# LinReg5_3V3.net
KiCad netlist of a schematic drawn in Altium Designer
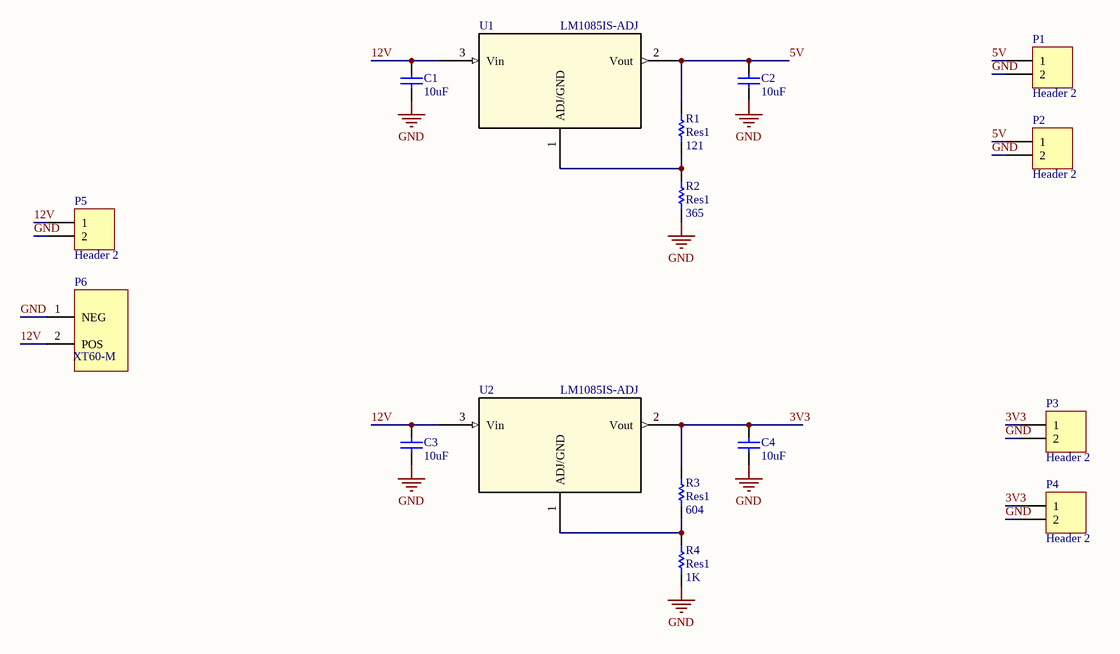
[diagram p0: LinReg5_3V3.SchDoc]

(export (version "E")
  (design (tool "Eeschema 10.0.6"))
  (components
    (comp (ref "C1")
      (value "10uF")
      (footprint "1206")
      (description "Capacitor")
      (fields (field (name "PUBLISHER") "Altium Limited"))
      (libsource (lib "Miscellaneous Devices") (part "Cap"))
    )
    (comp (ref "C2")
      (value "10uF")
      (footprint "1206")
      (description "Capacitor")
      (fields (field (name "PUBLISHER") "Altium Limited"))
      (libsource (lib "Miscellaneous Devices") (part "Cap"))
    )
    (comp (ref "C3")
      (value "10uF")
      (footprint "1206")
      (description "Capacitor")
      (fields (field (name "PUBLISHER") "Altium Limited"))
      (libsource (lib "Miscellaneous Devices") (part "Cap"))
    )
    (comp (ref "C4")
      (value "10uF")
      (footprint "1206")
      (description "Capacitor")
      (fields (field (name "PUBLISHER") "Altium Limited"))
      (libsource (lib "Miscellaneous Devices") (part "Cap"))
    )
    (comp (ref "P1")
      (value "Header 2")
      (footprint "HDR1X2")
      (description "Header, 2-Pin")
      (fields (field (name "PUBLISHER") "Altium Limited"))
      (libsource (lib "Miscellaneous Connectors") (part "Header 2"))
    )
    (comp (ref "P2")
      (value "Header 2")
      (footprint "HDR1X2")
      (description "Header, 2-Pin")
      (fields (field (name "PUBLISHER") "Altium Limited"))
      (libsource (lib "Miscellaneous Connectors") (part "Header 2"))
    )
    (comp (ref "P3")
      (value "Header 2")
      (footprint "HDR1X2")
      (description "Header, 2-Pin")
      (fields (field (name "PUBLISHER") "Altium Limited"))
      (libsource (lib "Miscellaneous Connectors") (part "Header 2"))
    )
    (comp (ref "P4")
      (value "Header 2")
      (footprint "HDR1X2")
      (description "Header, 2-Pin")
      (fields (field (name "PUBLISHER") "Altium Limited"))
      (libsource (lib "Miscellaneous Connectors") (part "Header 2"))
    )
    (comp (ref "P5")
      (value "Header 2")
      (footprint "HDR1X2")
      (description "Header, 2-Pin")
      (fields (field (name "PUBLISHER") "Altium Limited"))
      (libsource (lib "Miscellaneous Connectors") (part "Header 2"))
    )
    (comp (ref "P6")
      (value "XT60-M")
      (footprint "*AMASS_XT60-M")
      (description "Plug; DC supply; XT60; male; PIN: 2; for cable; soldered; 30A; 500V")
      (fields (field (name "MF") "AMASS"))
      (libsource (lib "XT60-M") (part "XT60-M"))
    )
    (comp (ref "R1")
      (value "Res1")
      (footprint "6-0805_N")
      (description "Resistor")
      (fields (field (name "ALTIUM_VALUE") "121") (field (name "PUBLISHER") "Altium Limited"))
      (libsource (lib "Miscellaneous Devices") (part "Res1"))
    )
    (comp (ref "R2")
      (value "Res1")
      (footprint "6-0805_N")
      (description "Resistor")
      (fields (field (name "ALTIUM_VALUE") "365") (field (name "PUBLISHER") "Altium Limited"))
      (libsource (lib "Miscellaneous Devices") (part "Res1"))
    )
    (comp (ref "R3")
      (value "Res1")
      (footprint "6-0805_N")
      (description "Resistor")
      (fields (field (name "ALTIUM_VALUE") "604") (field (name "PUBLISHER") "Altium Limited"))
      (libsource (lib "Miscellaneous Devices") (part "Res1"))
    )
    (comp (ref "R4")
      (value "Res1")
      (footprint "6-0805_N")
      (description "Resistor")
      (fields (field (name "ALTIUM_VALUE") "1K") (field (name "PUBLISHER") "Altium Limited"))
      (libsource (lib "Miscellaneous Devices") (part "Res1"))
    )
    (comp (ref "U1")
      (value "LM1085IS-ADJ")
      (footprint "TS3B")
      (description "No Description Available")
      (fields
        (field (name "MANUFACTURER_PART_NUMBER") "LM1085IS-ADJ/NOPB")
        (field (name "COPYRIGHT") "Copyright (C) 2018 Accelerated Designs. All rights reserved")
      )
      (libsource (lib "2020-03-17_20-39-12") (part "LM1085IS-ADJ/NOP"))
    )
    (comp (ref "U2")
      (value "LM1085IS-ADJ")
      (footprint "TS3B")
      (description "No Description Available")
      (fields
        (field (name "MANUFACTURER_PART_NUMBER") "LM1085IS-ADJ/NOPB")
        (field (name "COPYRIGHT") "Copyright (C) 2018 Accelerated Designs. All rights reserved")
      )
      (libsource (lib "2020-03-17_20-39-12") (part "LM1085IS-ADJ/NOP"))
    )
  )
  (nets
    (net (code "1") (name "/3V3") (class "Default")
      (node (ref "C4") (pin "2") (pinfunction "2_2") (pintype "passive"))
      (node (ref "P3") (pin "1") (pinfunction "1_1") (pintype "passive"))
      (node (ref "P4") (pin "1") (pinfunction "1_1") (pintype "passive"))
      (node (ref "R3") (pin "2") (pinfunction "2_2") (pintype "passive"))
      (node (ref "U2") (pin "2") (pinfunction "Vout_2") (pintype "output"))
    )
    (net (code "2") (name "/5V") (class "Default")
      (node (ref "C2") (pin "2") (pinfunction "2_2") (pintype "passive"))
      (node (ref "P1") (pin "1") (pinfunction "1_1") (pintype "passive"))
      (node (ref "P2") (pin "1") (pinfunction "1_1") (pintype "passive"))
      (node (ref "R1") (pin "2") (pinfunction "2_2") (pintype "passive"))
      (node (ref "U1") (pin "2") (pinfunction "Vout_2") (pintype "output"))
    )
    (net (code "3") (name "/12V") (class "Default")
      (node (ref "C1") (pin "2") (pinfunction "2_2") (pintype "passive"))
      (node (ref "C3") (pin "2") (pinfunction "2_2") (pintype "passive"))
      (node (ref "P5") (pin "1") (pinfunction "1_1") (pintype "passive"))
      (node (ref "P6") (pin "2") (pinfunction "POS_2") (pintype "passive"))
      (node (ref "U1") (pin "3") (pinfunction "Vin_3") (pintype "input"))
      (node (ref "U2") (pin "3") (pinfunction "Vin_3") (pintype "input"))
    )
    (net (code "4") (name "GND") (class "Default")
      (node (ref "C1") (pin "1") (pinfunction "1_1") (pintype "passive"))
      (node (ref "C2") (pin "1") (pinfunction "1_1") (pintype "passive"))
      (node (ref "C3") (pin "1") (pinfunction "1_1") (pintype "passive"))
      (node (ref "C4") (pin "1") (pinfunction "1_1") (pintype "passive"))
      (node (ref "P1") (pin "2") (pinfunction "2_2") (pintype "passive"))
      (node (ref "P2") (pin "2") (pinfunction "2_2") (pintype "passive"))
      (node (ref "P3") (pin "2") (pinfunction "2_2") (pintype "passive"))
      (node (ref "P4") (pin "2") (pinfunction "2_2") (pintype "passive"))
      (node (ref "P5") (pin "2") (pinfunction "2_2") (pintype "passive"))
      (node (ref "P6") (pin "1") (pinfunction "NEG_1") (pintype "passive"))
      (node (ref "R2") (pin "1") (pinfunction "1_1") (pintype "passive"))
      (node (ref "R4") (pin "1") (pinfunction "1_1") (pintype "passive"))
    )
    (net (code "5") (name "Net-(U1-ADJ{slash}GND)") (class "Default")
      (node (ref "R1") (pin "1") (pinfunction "1_1") (pintype "passive"))
      (node (ref "R2") (pin "2") (pinfunction "2_2") (pintype "passive"))
      (node (ref "U1") (pin "1") (pinfunction "ADJ/GND_1") (pintype "passive"))
    )
    (net (code "6") (name "Net-(U2-ADJ{slash}GND)") (class "Default")
      (node (ref "R3") (pin "1") (pinfunction "1_1") (pintype "passive"))
      (node (ref "R4") (pin "2") (pinfunction "2_2") (pintype "passive"))
      (node (ref "U2") (pin "1") (pinfunction "ADJ/GND_1") (pintype "passive"))
    )
  )
)
